# twinklr_board_5v.net
KiCad netlist of a schematic drawn in EAGLE
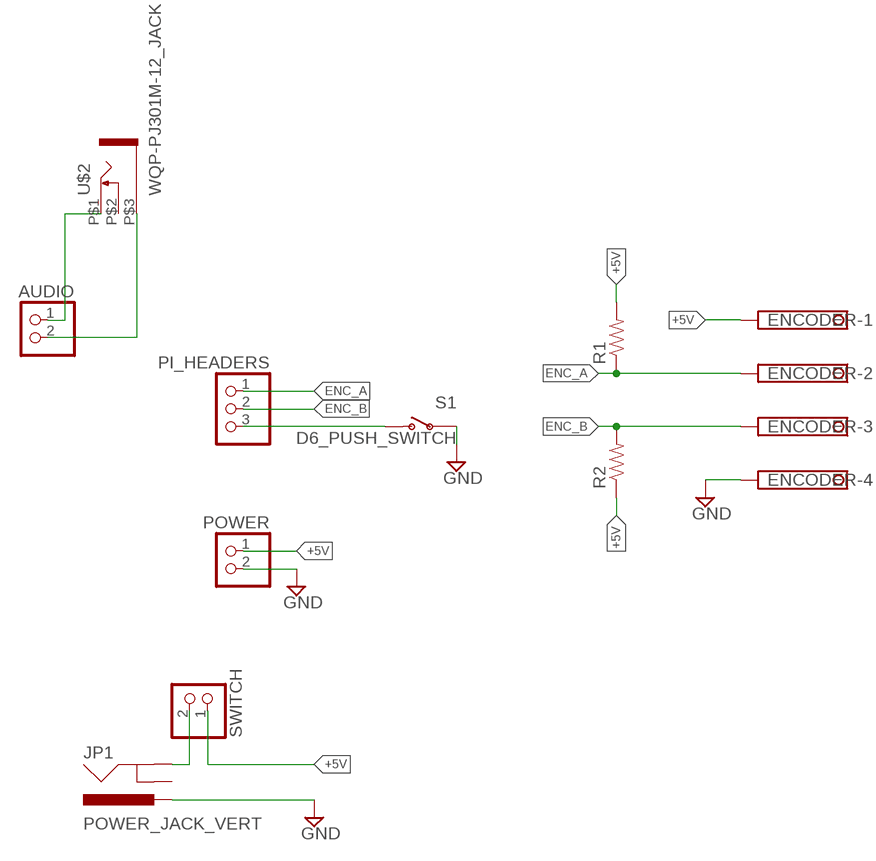
[diagram p0: schematic, sheet 1]

(export (version "E")
  (design (tool "Eeschema 10.0.6"))
  (components
    (comp (ref "AUDIO")
      (value "PINHD-1X2")
      (footprint "eagle-import:1X02")
      (libsource (lib "eagle-import") (part "PINHD-1X2"))
    )
    (comp (ref "ENCODER")
      (value "1751264")
      (footprint "eagle-import:1751264")
      (libsource (lib "eagle-import") (part "1751264"))
    )
    (comp (ref "JP1")
      (value "POWER_JACK_VERT")
      (footprint "eagle-import:POWER_JACK_VERT")
      (libsource (lib "eagle-import") (part "POWER_JACK_VERT"))
    )
    (comp (ref "PI_HEADERS")
      (value "PINHD-1X3")
      (footprint "eagle-import:1X03")
      (libsource (lib "eagle-import") (part "PINHD-1X3"))
    )
    (comp (ref "POWER")
      (value "PINHD-1X2")
      (footprint "eagle-import:1X02")
      (libsource (lib "eagle-import") (part "PINHD-1X2"))
    )
    (comp (ref "R1")
      (value "RESISTORAXIAL-0.3")
      (footprint "eagle-import:AXIAL-0.3")
      (libsource (lib "eagle-import") (part "RESISTORAXIAL-0.3"))
    )
    (comp (ref "R2")
      (value "RESISTORAXIAL-0.3")
      (footprint "eagle-import:AXIAL-0.3")
      (libsource (lib "eagle-import") (part "RESISTORAXIAL-0.3"))
    )
    (comp (ref "S1")
      (value "D6_PUSH_SWITCH")
      (footprint "eagle-import:D6_PUSH_SWITCH")
      (libsource (lib "eagle-import") (part "D6_PUSH_SWITCH"))
    )
    (comp (ref "SWITCH")
      (value "PINHD-1X2")
      (footprint "eagle-import:1X02")
      (libsource (lib "eagle-import") (part "PINHD-1X2"))
    )
    (comp (ref "U$2")
      (value "WQP-PJ301M-12_JACK")
      (footprint "eagle-import:WQP-PJ301M-12_JACK")
      (libsource (lib "eagle-import") (part "WQP-PJ301M-12_JACK"))
    )
  )
  (nets
    (net (code "1") (name "+5V") (class "Default")
      (node (ref "ENCODER") (pin "1") (pinfunction "K_1") (pintype "passive"))
      (node (ref "POWER") (pin "1") (pinfunction "1_1") (pintype "passive"))
      (node (ref "R1") (pin "P$2") (pinfunction "2_P$2") (pintype "passive"))
      (node (ref "R2") (pin "P$1") (pinfunction "1_P$1") (pintype "passive"))
      (node (ref "SWITCH") (pin "1") (pinfunction "1_1") (pintype "passive"))
    )
    (net (code "2") (name "ENC_A") (class "Default")
      (node (ref "ENCODER") (pin "2") (pinfunction "K_2") (pintype "passive"))
      (node (ref "PI_HEADERS") (pin "1") (pinfunction "1_1") (pintype "passive"))
      (node (ref "R1") (pin "P$1") (pinfunction "1_P$1") (pintype "passive"))
    )
    (net (code "3") (name "ENC_B") (class "Default")
      (node (ref "ENCODER") (pin "3") (pinfunction "K_3") (pintype "passive"))
      (node (ref "PI_HEADERS") (pin "2") (pinfunction "2_2") (pintype "passive"))
      (node (ref "R2") (pin "P$2") (pinfunction "2_P$2") (pintype "passive"))
    )
    (net (code "4") (name "GND") (class "Default")
      (node (ref "ENCODER") (pin "4") (pinfunction "K_4") (pintype "passive"))
      (node (ref "JP1") (pin "PWR") (pinfunction "PWR_PWR") (pintype "bidirectional"))
      (node (ref "POWER") (pin "2") (pinfunction "2_2") (pintype "passive"))
      (node (ref "S1") (pin "P$3") (pinfunction "P_P$3") (pintype "passive"))
      (node (ref "S1") (pin "P$4") (pinfunction "P_P$4") (pintype "passive"))
    )
    (net (code "5") (name "Net-(JP1-PadGND)") (class "Default")
      (node (ref "JP1") (pin "GND") (pinfunction "GND_GND") (pintype "bidirectional"))
      (node (ref "SWITCH") (pin "2") (pinfunction "2_2") (pintype "passive"))
    )
    (net (code "6") (name "Net-(PI_HEADERS-Pad3)") (class "Default")
      (node (ref "PI_HEADERS") (pin "3") (pinfunction "3_3") (pintype "passive"))
      (node (ref "S1") (pin "P$1") (pinfunction "O_P$1") (pintype "passive"))
      (node (ref "S1") (pin "P$2") (pinfunction "O_P$2") (pintype "passive"))
    )
    (net (code "7") (name "Net-(U$2-1)") (class "Default")
      (node (ref "AUDIO") (pin "2") (pinfunction "2_2") (pintype "passive"))
      (node (ref "U$2") (pin "P$3") (pinfunction "1_P$3") (pintype "passive"))
    )
    (net (code "8") (name "Net-(U$2-2)") (class "Default")
      (node (ref "AUDIO") (pin "1") (pinfunction "1_1") (pintype "passive"))
      (node (ref "U$2") (pin "P$1") (pinfunction "2_P$1") (pintype "passive"))
    )
    (net (code "9") (name "unconnected-(JP1-PadGNDBREAK)") (class "Default")
      (node (ref "JP1") (pin "GNDBREAK") (pinfunction "GNDBREAK_GNDBREAK") (pintype "bidirectional"))
    )
    (net (code "10") (name "unconnected-(U$2-3-PadP$2)") (class "Default")
      (node (ref "U$2") (pin "P$2") (pinfunction "3_P$2") (pintype "passive"))
    )
  )
)
